# Com.net
KiCad netlist of a schematic drawn in Altium Designer
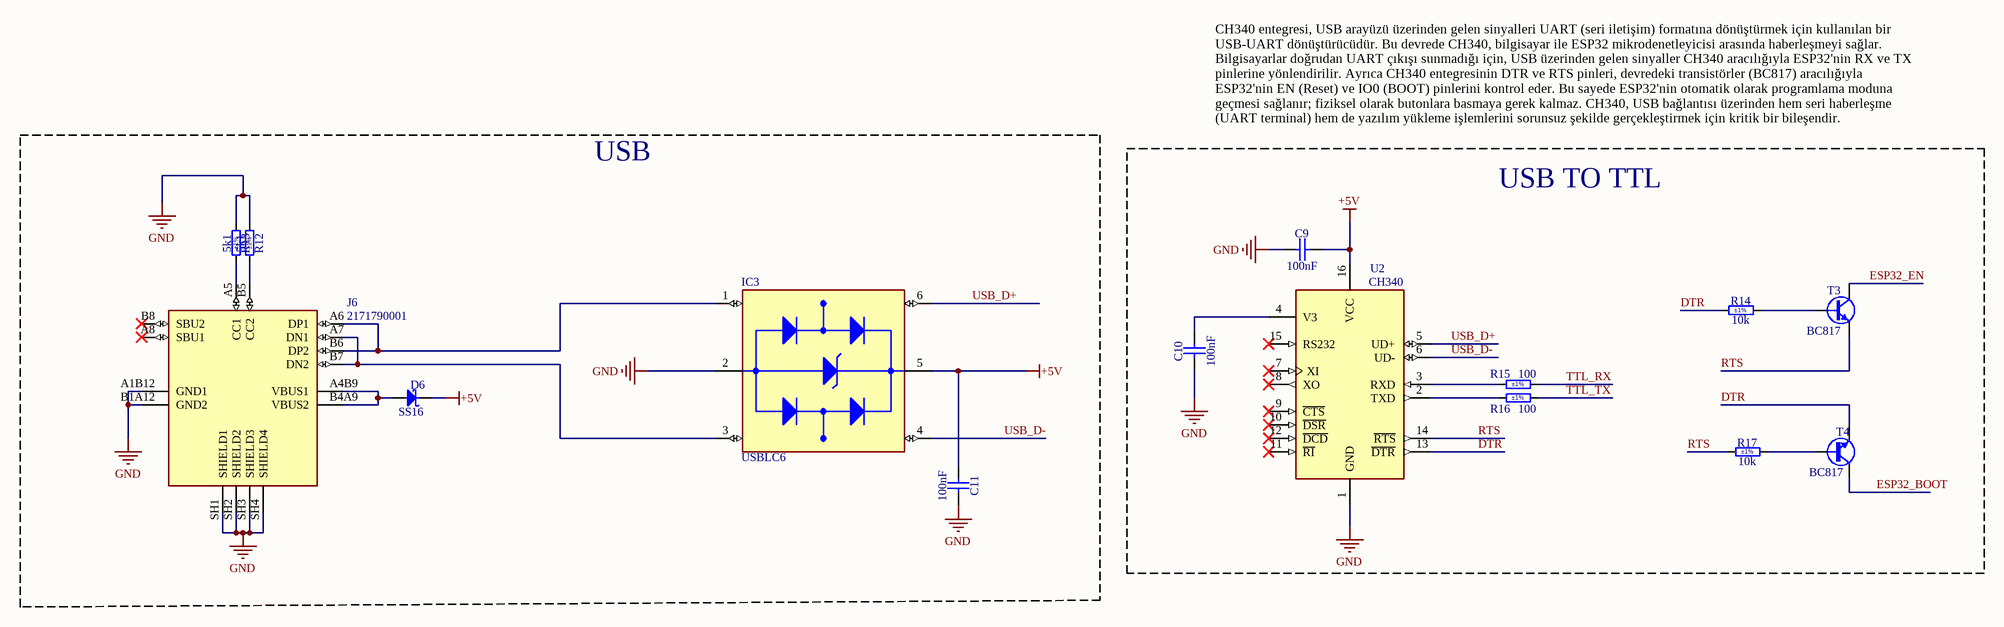
[diagram p0: Com.SchDoc]

(export (version "E")
  (design (tool "Eeschema 10.0.6"))
  (components
    (comp (ref "C9")
      (value "100nF")
      (footprint "CAPC1608X87N")
      (description "Non-polarised capacitor")
      (fields
        (field (name "PART NUMBER") "CC0603_100NF_50V_10%_X5R")
        (field (name "VOLTAGE") "50V")
        (field (name "AUTHOR") "CERN DEM MR")
      )
      (libsource (lib "Capacitors") (part "Capacitor - non polarized"))
    )
    (comp (ref "C10")
      (value "100nF")
      (footprint "CAPC1608X87N")
      (description "Non-polarised capacitor")
      (fields
        (field (name "PART NUMBER") "CC0603_100NF_50V_10%_X5R")
        (field (name "VOLTAGE") "50V")
        (field (name "AUTHOR") "CERN DEM MR")
      )
      (libsource (lib "Capacitors") (part "Capacitor - non polarized"))
    )
    (comp (ref "C11")
      (value "100nF")
      (footprint "CAPC1608X87N")
      (description "Non-polarised capacitor")
      (fields
        (field (name "PART NUMBER") "CC0603_100NF_50V_10%_X5R")
        (field (name "VOLTAGE") "50V")
        (field (name "AUTHOR") "CERN DEM MR")
      )
      (libsource (lib "Capacitors") (part "Capacitor - non polarized"))
    )
    (comp (ref "D6")
      (value "SS16")
      (footprint "DIOM5127X229N")
      (description "Schottky Diode")
      (fields
        (field (name "VOLTAGE") "60V")
        (field (name "POWER") "1A")
        (field (name "AUTHOR") "CERN DEM JLC")
      )
      (libsource (lib "ICs And Semiconductors") (part "Diode Schottky"))
    )
    (comp (ref "IC3") (value "USBLC6") (footprint "USBC6") (libsource (lib "Schlib1") (part "USBLC6")))
    (comp (ref "J6")
      (value "2171790001")
      (footprint "TYPEC")
      (libsource (lib "Tansa_Server_Schematic_Library") (part "TypeC USB2.0 16pin SMD"))
    )
    (comp (ref "R12")
      (value "5k1")
      (footprint "RESC1608X55N")
      (description "Resistor - 1%")
      (fields
        (field (name "TOLERANCE") "±1%")
        (field (name "PART NUMBER") "R0603_5K1_1%_0.1W_100PPM")
        (field (name "POWER") "0.1W")
        (field (name "AUTHOR") "CERN DEM JLC")
      )
      (libsource (lib "Resistors") (part "Resistor - 1%"))
    )
    (comp (ref "R13")
      (value "5k1")
      (footprint "RESC1608X55N")
      (description "Resistor - 1%")
      (fields
        (field (name "TOLERANCE") "±1%")
        (field (name "PART NUMBER") "R0603_5K1_1%_0.1W_100PPM")
        (field (name "POWER") "0.1W")
        (field (name "AUTHOR") "CERN DEM JLC")
      )
      (libsource (lib "Resistors") (part "Resistor - 1%"))
    )
    (comp (ref "R14")
      (value "10k")
      (footprint "RESC1608X55N")
      (description "Resistor - 1%")
      (fields
        (field (name "TOLERANCE") "±1%")
        (field (name "PART NUMBER") "R0603_10K_1%_0.1W_100PPM")
        (field (name "POWER") "0.1W")
        (field (name "AUTHOR") "CERN DEM JLC")
      )
      (libsource (lib "Resistors") (part "Resistor - 1%"))
    )
    (comp (ref "R15")
      (value "100")
      (footprint "RESC1608X55N")
      (description "Resistor - 1%")
      (fields
        (field (name "TOLERANCE") "±1%")
        (field (name "PART NUMBER") "R0603_100R_1%_0.1W_100PPM")
        (field (name "POWER") "0.1W")
        (field (name "AUTHOR") "CERN DEM JLC")
      )
      (libsource (lib "Resistors") (part "Resistor - 1%"))
    )
    (comp (ref "R16")
      (value "100")
      (footprint "RESC1608X55N")
      (description "Resistor - 1%")
      (fields
        (field (name "TOLERANCE") "±1%")
        (field (name "PART NUMBER") "R0603_100R_1%_0.1W_100PPM")
        (field (name "POWER") "0.1W")
        (field (name "AUTHOR") "CERN DEM JLC")
      )
      (libsource (lib "Resistors") (part "Resistor - 1%"))
    )
    (comp (ref "R17")
      (value "10k")
      (footprint "RESC1608X55N")
      (description "Resistor - 1%")
      (fields
        (field (name "TOLERANCE") "±1%")
        (field (name "PART NUMBER") "R0603_10K_1%_0.1W_100PPM")
        (field (name "POWER") "0.1W")
        (field (name "AUTHOR") "CERN DEM JLC")
      )
      (libsource (lib "Resistors") (part "Resistor - 1%"))
    )
    (comp (ref "T3")
      (value "BC817")
      (footprint "SOT95P230X110-3N")
      (description "NPN Transistor")
      (fields (field (name "MANUFACTURER") "NXP SEMICONDUCTORS") (field (name "AUTHOR") "CERN DEM JLC"))
      (libsource (lib "ICs And Semiconductors") (part "NPN B1 E2 C3"))
    )
    (comp (ref "T4")
      (value "BC817")
      (footprint "SOT95P230X110-3N")
      (description "NPN Transistor")
      (fields (field (name "MANUFACTURER") "NXP SEMICONDUCTORS") (field (name "AUTHOR") "CERN DEM JLC"))
      (libsource (lib "ICs And Semiconductors") (part "NPN B1 E2 C3"))
    )
    (comp (ref "U2") (value "CH340") (footprint "CH340") (libsource (lib "Schlib1") (part "CH340")))
  )
  (nets
    (net (code "1") (name "+5V") (class "Default")
      (node (ref "C11") (pin "2") (pinfunction "2_2") (pintype "passive"))
      (node (ref "C9") (pin "2") (pinfunction "2_2") (pintype "passive"))
      (node (ref "D6") (pin "1") (pinfunction "C_1") (pintype "passive"))
      (node (ref "IC3") (pin "5") (pinfunction "VBUS_5") (pintype "power_in"))
      (node (ref "U2") (pin "16") (pinfunction "VCC_16") (pintype "power_in"))
    )
    (net (code "3") (name "/DTR") (class "Default")
      (node (ref "R14") (pin "1") (pinfunction "1_1") (pintype "passive"))
      (node (ref "T4") (pin "2") (pinfunction "E_2") (pintype "passive"))
      (node (ref "U2") (pin "13") (pinfunction "~{DTR}_13") (pintype "output"))
    )
    (net (code "4") (name "/ESP32_BOOT") (class "Default")
      (node (ref "T4") (pin "3") (pinfunction "C_3") (pintype "passive"))
    )
    (net (code "5") (name "/ESP32_EN") (class "Default")
      (node (ref "T3") (pin "3") (pinfunction "C_3") (pintype "passive"))
    )
    (net (code "6") (name "/RTS") (class "Default")
      (node (ref "R17") (pin "1") (pinfunction "1_1") (pintype "passive"))
      (node (ref "T3") (pin "2") (pinfunction "E_2") (pintype "passive"))
      (node (ref "U2") (pin "14") (pinfunction "~{RTS}_14") (pintype "output"))
    )
    (net (code "7") (name "/TTL_RX") (class "Default")
      (node (ref "R15") (pin "2") (pinfunction "2_2") (pintype "passive"))
    )
    (net (code "8") (name "/TTL_TX") (class "Default")
      (node (ref "R16") (pin "2") (pinfunction "2_2") (pintype "passive"))
    )
    (net (code "9") (name "/USB_D+") (class "Default")
      (node (ref "IC3") (pin "6") (pinfunction "I/O1_OUT_6") (pintype "bidirectional"))
      (node (ref "U2") (pin "5") (pinfunction "UD+_5") (pintype "bidirectional"))
    )
    (net (code "10") (name "/USB_D-") (class "Default")
      (node (ref "IC3") (pin "4") (pinfunction "I/O2_OUT_4") (pintype "bidirectional"))
      (node (ref "U2") (pin "6") (pinfunction "UD-_6") (pintype "bidirectional"))
    )
    (net (code "11") (name "GND") (class "Default")
      (node (ref "C10") (pin "1") (pinfunction "1_1") (pintype "passive"))
      (node (ref "C11") (pin "1") (pinfunction "1_1") (pintype "passive"))
      (node (ref "C9") (pin "1") (pinfunction "1_1") (pintype "passive"))
      (node (ref "IC3") (pin "2") (pinfunction "GND_2") (pintype "power_in"))
      (node (ref "J6") (pin "A1B12") (pinfunction "GND1_A1B12") (pintype "power_in"))
      (node (ref "J6") (pin "B1A12") (pinfunction "GND2_B1A12") (pintype "power_in"))
      (node (ref "J6") (pin "SH1") (pinfunction "SHIELD1_SH1") (pintype "passive"))
      (node (ref "J6") (pin "SH2") (pinfunction "SHIELD2_SH2") (pintype "passive"))
      (node (ref "J6") (pin "SH3") (pinfunction "SHIELD3_SH3") (pintype "passive"))
      (node (ref "J6") (pin "SH4") (pinfunction "SHIELD4_SH4") (pintype "passive"))
      (node (ref "R12") (pin "2") (pinfunction "2_2") (pintype "passive"))
      (node (ref "R13") (pin "2") (pinfunction "2_2") (pintype "passive"))
      (node (ref "U2") (pin "1") (pinfunction "GND_1") (pintype "power_in"))
    )
    (net (code "12") (name "Net-(D6-A)") (class "Default")
      (node (ref "D6") (pin "2") (pinfunction "A_2") (pintype "passive"))
      (node (ref "J6") (pin "A4B9") (pinfunction "VBUS1_A4B9") (pintype "power_in"))
      (node (ref "J6") (pin "B4A9") (pinfunction "VBUS2_B4A9") (pintype "power_in"))
    )
    (net (code "13") (name "Net-(IC3-I{slash}O1_IN)") (class "Default")
      (node (ref "IC3") (pin "1") (pinfunction "I/O1_IN_1") (pintype "bidirectional"))
      (node (ref "J6") (pin "A6") (pinfunction "DP1_A6") (pintype "bidirectional"))
      (node (ref "J6") (pin "B6") (pinfunction "DP2_B6") (pintype "bidirectional"))
    )
    (net (code "14") (name "Net-(IC3-I{slash}O2_IN)") (class "Default")
      (node (ref "IC3") (pin "3") (pinfunction "I/O2_IN_3") (pintype "bidirectional"))
      (node (ref "J6") (pin "A7") (pinfunction "DN1_A7") (pintype "bidirectional"))
      (node (ref "J6") (pin "B7") (pinfunction "DN2_B7") (pintype "bidirectional"))
    )
    (net (code "15") (name "Net-(J6-CC1)") (class "Default")
      (node (ref "J6") (pin "A5") (pinfunction "CC1_A5") (pintype "bidirectional"))
      (node (ref "R13") (pin "1") (pinfunction "1_1") (pintype "passive"))
    )
    (net (code "16") (name "Net-(J6-CC2)") (class "Default")
      (node (ref "J6") (pin "B5") (pinfunction "CC2_B5") (pintype "bidirectional"))
      (node (ref "R12") (pin "1") (pinfunction "1_1") (pintype "passive"))
    )
    (net (code "17") (name "Net-(T3-B)") (class "Default")
      (node (ref "R14") (pin "2") (pinfunction "2_2") (pintype "passive"))
      (node (ref "T3") (pin "1") (pinfunction "B_1") (pintype "passive"))
    )
    (net (code "18") (name "Net-(T4-B)") (class "Default")
      (node (ref "R17") (pin "2") (pinfunction "2_2") (pintype "passive"))
      (node (ref "T4") (pin "1") (pinfunction "B_1") (pintype "passive"))
    )
    (net (code "19") (name "Net-(U2-RXD)") (class "Default")
      (node (ref "R15") (pin "1") (pinfunction "1_1") (pintype "passive"))
      (node (ref "U2") (pin "3") (pinfunction "RXD_3") (pintype "input"))
    )
    (net (code "20") (name "Net-(U2-TXD)") (class "Default")
      (node (ref "R16") (pin "1") (pinfunction "1_1") (pintype "passive"))
      (node (ref "U2") (pin "2") (pinfunction "TXD_2") (pintype "output"))
    )
    (net (code "21") (name "Net-(U2-V3)") (class "Default")
      (node (ref "C10") (pin "2") (pinfunction "2_2") (pintype "passive"))
      (node (ref "U2") (pin "4") (pinfunction "V3_4") (pintype "power_in"))
    )
    (net (code "22") (name "unconnected-(J6-SBU1-PadA8)") (class "Default")
      (node (ref "J6") (pin "A8") (pinfunction "SBU1_A8") (pintype "bidirectional+no_connect"))
    )
    (net (code "23") (name "unconnected-(J6-SBU2-PadB8)") (class "Default")
      (node (ref "J6") (pin "B8") (pinfunction "SBU2_B8") (pintype "bidirectional+no_connect"))
    )
    (net (code "24") (name "unconnected-(U2-RS232-Pad15)") (class "Default")
      (node (ref "U2") (pin "15") (pinfunction "RS232_15") (pintype "input+no_connect"))
    )
    (net (code "25") (name "unconnected-(U2-XI-Pad7)") (class "Default")
      (node (ref "U2") (pin "7") (pinfunction "XI_7") (pintype "input+no_connect"))
    )
    (net (code "26") (name "unconnected-(U2-XO-Pad8)") (class "Default")
      (node (ref "U2") (pin "8") (pinfunction "XO_8") (pintype "output+no_connect"))
    )
    (net (code "27") (name "unconnected-(U2-~{CTS}-Pad9)") (class "Default")
      (node (ref "U2") (pin "9") (pinfunction "~{CTS}_9") (pintype "input+no_connect"))
    )
    (net (code "28") (name "unconnected-(U2-~{DCD}-Pad12)") (class "Default")
      (node (ref "U2") (pin "12") (pinfunction "~{DCD}_12") (pintype "input+no_connect"))
    )
    (net (code "29") (name "unconnected-(U2-~{DSR}-Pad10)") (class "Default")
      (node (ref "U2") (pin "10") (pinfunction "~{DSR}_10") (pintype "input+no_connect"))
    )
    (net (code "30") (name "unconnected-(U2-~{RI}-Pad11)") (class "Default")
      (node (ref "U2") (pin "11") (pinfunction "~{RI}_11") (pintype "input+no_connect"))
    )
  )
)
